# LCmeter0-LCD-8pinlcd-PIC-COMP.net
KiCad netlist of a schematic drawn in EAGLE
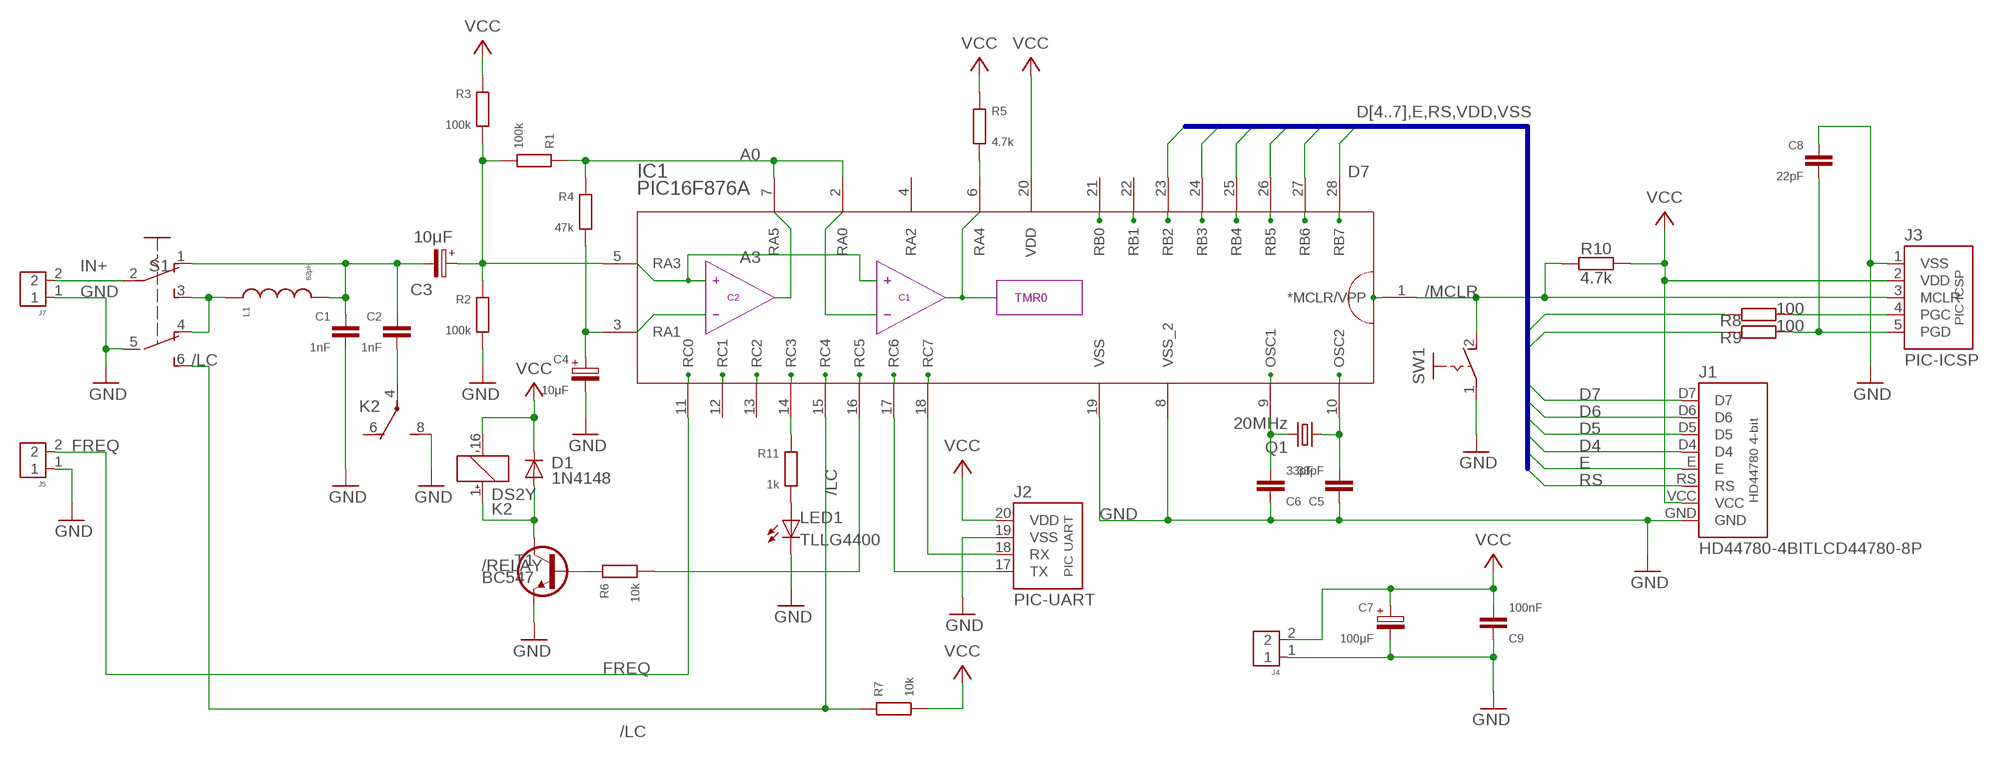
[diagram p0: schematic, sheet 1]

(export (version "E")
  (design (tool "Eeschema 10.0.6"))
  (components
    (comp (ref "C1")
      (value "1nF")
      (footprint "eagle-import:C050-025X060")
      (libsource (lib "eagle-import") (part "C025-025X060"))
    )
    (comp (ref "C2")
      (value "1nF")
      (footprint "eagle-import:C050-025X060")
      (libsource (lib "eagle-import") (part "C025-025X060"))
    )
    (comp (ref "C3")
      (value "10μF")
      (footprint "eagle-import:E2,5-4")
      (libsource (lib "eagle-import") (part "CPOLE2,5-4"))
    )
    (comp (ref "C4")
      (value "10μF")
      (footprint "eagle-import:E2,5-4")
      (libsource (lib "eagle-import") (part "CPOLE2,5-4"))
    )
    (comp (ref "C5")
      (value "33pF")
      (footprint "eagle-import:C025-020X036")
      (libsource (lib "eagle-import") (part "C025-020X036"))
    )
    (comp (ref "C6")
      (value "33pF")
      (footprint "eagle-import:C025-020X036")
      (libsource (lib "eagle-import") (part "C025-020X036"))
    )
    (comp (ref "C7")
      (value "100μF")
      (footprint "eagle-import:E2,5-5")
      (libsource (lib "eagle-import") (part "CPOLE2.5-5"))
    )
    (comp (ref "C8")
      (value "22pF")
      (footprint "eagle-import:C050-020X036")
      (libsource (lib "eagle-import") (part "C050-020X036"))
    )
    (comp (ref "C9")
      (value "100nF")
      (footprint "eagle-import:C025-020X036_V")
      (libsource (lib "eagle-import") (part "C025-020X036/V"))
    )
    (comp (ref "D1")
      (value "1N4148")
      (footprint "eagle-import:DO34-7")
      (libsource (lib "eagle-import") (part "1N414834-7"))
    )
    (comp (ref "IC1")
      (value "PIC16F876A")
      (footprint "eagle-import:DIL28-3")
      (libsource (lib "eagle-import") (part "PIC16F876A-X/SP-COMP-B-A"))
    )
    (comp (ref "J1")
      (value "HD44780-4BITLCD44780-8P")
      (footprint "eagle-import:CONN-LCD44780")
      (libsource (lib "eagle-import") (part "HD44780-4BITLCD44780-8P"))
    )
    (comp (ref "J2")
      (value "PIC-UART")
      (footprint "eagle-import:PIC-UART")
      (libsource (lib "eagle-import") (part "PIC-UART"))
    )
    (comp (ref "J3")
      (value "PIC-ICSP")
      (footprint "eagle-import:PIC-ICSP")
      (libsource (lib "eagle-import") (part "PIC-ICSPICSP"))
    )
    (comp (ref "J4")
      (value "J4")
      (footprint "eagle-import:CONN-2P")
      (libsource (lib "eagle-import") (part "CONN-2P2P/H"))
    )
    (comp (ref "J5")
      (value "CONN-2P2P/V")
      (footprint "eagle-import:CONN-2P-V")
      (libsource (lib "eagle-import") (part "CONN-2P2P/V"))
    )
    (comp (ref "J7")
      (value "CONN-2P2P/V")
      (footprint "eagle-import:CONN-2P-V")
      (libsource (lib "eagle-import") (part "CONN-2P2P/V"))
    )
    (comp (ref "K2")
      (value "DS2Y")
      (footprint "eagle-import:DS2Y")
      (fields (field (name "MPN") "DS2Y-S-DC5V"))
      (libsource (lib "eagle-import") (part "DS2Y-S-DC5V"))
    )
    (comp (ref "L1")
      (value "82μH")
      (footprint "eagle-import:0207_10")
      (libsource (lib "eagle-import") (part "LAXIAL"))
    )
    (comp (ref "LED1")
      (value "TLLG4400")
      (footprint "eagle-import:LED3MM")
      (fields (field (name "MF") "VISHAY SEMICONDUCTOR"))
      (libsource (lib "eagle-import") (part "TLLG4400"))
    )
    (comp (ref "Q1")
      (value "20MHz")
      (footprint "eagle-import:HC49")
      (libsource (lib "eagle-import") (part "CRYSTALHC49"))
    )
    (comp (ref "R1")
      (value "100k")
      (footprint "eagle-import:0202_7")
      (libsource (lib "eagle-import") (part "R0202/7"))
    )
    (comp (ref "R2")
      (value "100k")
      (footprint "eagle-import:0202_7")
      (libsource (lib "eagle-import") (part "R0202/7"))
    )
    (comp (ref "R3")
      (value "100k")
      (footprint "eagle-import:0202_7")
      (libsource (lib "eagle-import") (part "R0202/7"))
    )
    (comp (ref "R4")
      (value "47k")
      (footprint "eagle-import:0202_7")
      (libsource (lib "eagle-import") (part "R0202/7"))
    )
    (comp (ref "R5")
      (value "4.7k")
      (footprint "eagle-import:0202_7")
      (libsource (lib "eagle-import") (part "R0202/7"))
    )
    (comp (ref "R6")
      (value "10k")
      (footprint "eagle-import:0202_7-V")
      (libsource (lib "eagle-import") (part "R0202/7-V"))
    )
    (comp (ref "R7")
      (value "10k")
      (footprint "eagle-import:0202_10-V")
      (libsource (lib "eagle-import") (part "R0202/10-V"))
    )
    (comp (ref "R8")
      (value "100")
      (footprint "eagle-import:0202_7-V")
      (libsource (lib "eagle-import") (part "R0202/7-V"))
    )
    (comp (ref "R9")
      (value "100")
      (footprint "eagle-import:0202_5-V")
      (libsource (lib "eagle-import") (part "R0202/5-V"))
    )
    (comp (ref "R10")
      (value "4.7k")
      (footprint "eagle-import:0202_7")
      (libsource (lib "eagle-import") (part "R0202/7"))
    )
    (comp (ref "R11")
      (value "1k")
      (footprint "eagle-import:0202_5-V")
      (libsource (lib "eagle-import") (part "R0202/5-V"))
    )
    (comp (ref "S1")
      (value "SL-SW-2P-2T")
      (footprint "eagle-import:SLSW-2P2T")
      (libsource (lib "eagle-import") (part "SL-SW-2P-2T"))
    )
    (comp (ref "SW1")
      (value "PB-1P-1T")
      (footprint "eagle-import:PB-1P1T")
      (libsource (lib "eagle-import") (part "PB-1P-1T"))
    )
    (comp (ref "T1")
      (value "BC547")
      (footprint "eagle-import:TO92-CBE-A")
      (libsource (lib "eagle-import") (part "BC547CBE-A"))
    )
  )
  (nets
    (net (code "3") (name "/A0") (class "Default")
      (node (ref "IC1") (pin "2") (pinfunction "RA0_2") (pintype "passive"))
      (node (ref "IC1") (pin "7") (pinfunction "RA5_7") (pintype "passive"))
      (node (ref "R1") (pin "2") (pinfunction "2_2") (pintype "passive"))
      (node (ref "R4") (pin "2") (pinfunction "2_2") (pintype "passive"))
    )
    (net (code "4") (name "/A3") (class "Default")
      (node (ref "C3") (pin "+") (pinfunction "+_+") (pintype "passive"))
      (node (ref "IC1") (pin "5") (pinfunction "RA3_5") (pintype "passive"))
      (node (ref "R1") (pin "1") (pinfunction "1_1") (pintype "passive"))
      (node (ref "R2") (pin "2") (pinfunction "2_2") (pintype "passive"))
      (node (ref "R3") (pin "1") (pinfunction "1_1") (pintype "passive"))
    )
    (net (code "5") (name "/D4") (class "Default")
      (node (ref "IC1") (pin "25") (pinfunction "RB4_25") (pintype "passive"))
      (node (ref "J1") (pin "D4") (pinfunction "D4_D4") (pintype "passive"))
    )
    (net (code "6") (name "/D5") (class "Default")
      (node (ref "IC1") (pin "26") (pinfunction "RB5_26") (pintype "passive"))
      (node (ref "J1") (pin "D5") (pinfunction "D5_D5") (pintype "passive"))
    )
    (net (code "7") (name "/D6") (class "Default")
      (node (ref "IC1") (pin "27") (pinfunction "RB6_27") (pintype "passive"))
      (node (ref "J1") (pin "D6") (pinfunction "D6_D6") (pintype "passive"))
      (node (ref "R8") (pin "2") (pinfunction "2_2") (pintype "passive"))
    )
    (net (code "8") (name "/D7") (class "Default")
      (node (ref "IC1") (pin "28") (pinfunction "RB7_28") (pintype "passive"))
      (node (ref "J1") (pin "D7") (pinfunction "D7_D7") (pintype "passive"))
      (node (ref "R9") (pin "2") (pinfunction "2_2") (pintype "passive"))
    )
    (net (code "9") (name "/E") (class "Default")
      (node (ref "IC1") (pin "24") (pinfunction "RB3_24") (pintype "passive"))
      (node (ref "J1") (pin "E") (pinfunction "E_E") (pintype "passive"))
    )
    (net (code "10") (name "/FREQ") (class "Default")
      (node (ref "IC1") (pin "11") (pinfunction "RC0_11") (pintype "passive"))
      (node (ref "J5") (pin "2") (pinfunction "2_2") (pintype "bidirectional"))
    )
    (net (code "11") (name "/IN+") (class "Default")
      (node (ref "J7") (pin "2") (pinfunction "2_2") (pintype "bidirectional"))
      (node (ref "S1") (pin "2") (pinfunction "P_2") (pintype "passive"))
    )
    (net (code "12") (name "/RS") (class "Default")
      (node (ref "IC1") (pin "23") (pinfunction "RB2_23") (pintype "passive"))
      (node (ref "J1") (pin "RS") (pinfunction "RS_RS") (pintype "passive"))
    )
    (net (code "14") (name "/{slash}LC") (class "Default")
      (node (ref "IC1") (pin "15") (pinfunction "RC4_15") (pintype "passive"))
      (node (ref "R7") (pin "2") (pinfunction "2_2") (pintype "passive"))
      (node (ref "S1") (pin "6") (pinfunction "S1_6") (pintype "passive"))
    )
    (net (code "15") (name "/{slash}MCLR") (class "Default")
      (node (ref "IC1") (pin "1") (pinfunction "*MCLR/VPP_1") (pintype "passive"))
      (node (ref "J3") (pin "3") (pinfunction "MCLR_3") (pintype "passive"))
      (node (ref "R10") (pin "2") (pinfunction "2_2") (pintype "passive"))
      (node (ref "SW1") (pin "2") (pinfunction "S_2") (pintype "passive"))
    )
    (net (code "16") (name "/{slash}RELAY") (class "Default")
      (node (ref "D1") (pin "A") (pinfunction "A_A") (pintype "passive"))
      (node (ref "K2") (pin "1") (pinfunction "+_1") (pintype "passive"))
      (node (ref "T1") (pin "C") (pinfunction "C_C") (pintype "passive"))
    )
    (net (code "17") (name "GND") (class "Default")
      (node (ref "C1") (pin "2") (pinfunction "2_2") (pintype "passive"))
      (node (ref "C4") (pin "-") (pinfunction "-_-") (pintype "passive"))
      (node (ref "C5") (pin "1") (pinfunction "1_1") (pintype "passive"))
      (node (ref "C6") (pin "1") (pinfunction "1_1") (pintype "passive"))
      (node (ref "C7") (pin "-") (pinfunction "-_-") (pintype "passive"))
      (node (ref "C8") (pin "1") (pinfunction "1_1") (pintype "passive"))
      (node (ref "C9") (pin "1") (pinfunction "1_1") (pintype "passive"))
      (node (ref "IC1") (pin "19") (pinfunction "VSS_19") (pintype "passive"))
      (node (ref "IC1") (pin "8") (pinfunction "VSS_2_8") (pintype "passive"))
      (node (ref "J1") (pin "GND") (pinfunction "GND_GND") (pintype "passive"))
      (node (ref "J2") (pin "19") (pinfunction "VSS_19") (pintype "passive"))
      (node (ref "J3") (pin "1") (pinfunction "VSS_1") (pintype "passive"))
      (node (ref "J4") (pin "1") (pinfunction "1_1") (pintype "bidirectional"))
      (node (ref "J5") (pin "1") (pinfunction "1_1") (pintype "bidirectional"))
      (node (ref "J7") (pin "1") (pinfunction "1_1") (pintype "bidirectional"))
      (node (ref "K2") (pin "8") (pinfunction "S_8") (pintype "passive"))
      (node (ref "LED1") (pin "K") (pinfunction "C_K") (pintype "passive"))
      (node (ref "R2") (pin "1") (pinfunction "1_1") (pintype "passive"))
      (node (ref "S1") (pin "5") (pinfunction "P1_5") (pintype "passive"))
      (node (ref "SW1") (pin "1") (pinfunction "P_1") (pintype "passive"))
      (node (ref "T1") (pin "E") (pinfunction "E_E") (pintype "passive"))
    )
    (net (code "18") (name "Net-(IC1-OSC1)") (class "Default")
      (node (ref "C6") (pin "2") (pinfunction "2_2") (pintype "passive"))
      (node (ref "IC1") (pin "9") (pinfunction "OSC1_9") (pintype "passive"))
      (node (ref "Q1") (pin "2") (pinfunction "2_2") (pintype "passive"))
    )
    (net (code "19") (name "Net-(IC1-OSC2)") (class "Default")
      (node (ref "C5") (pin "2") (pinfunction "2_2") (pintype "passive"))
      (node (ref "IC1") (pin "10") (pinfunction "OSC2_10") (pintype "passive"))
      (node (ref "Q1") (pin "1") (pinfunction "1_1") (pintype "passive"))
    )
    (net (code "20") (name "Net-(IC1-RA1)") (class "Default")
      (node (ref "C4") (pin "+") (pinfunction "+_+") (pintype "passive"))
      (node (ref "IC1") (pin "3") (pinfunction "RA1_3") (pintype "passive"))
      (node (ref "R4") (pin "1") (pinfunction "1_1") (pintype "passive"))
    )
    (net (code "21") (name "Net-(IC1-RA4)") (class "Default")
      (node (ref "IC1") (pin "6") (pinfunction "RA4_6") (pintype "passive"))
      (node (ref "R5") (pin "1") (pinfunction "1_1") (pintype "passive"))
    )
    (net (code "22") (name "Net-(IC1-RC3)") (class "Default")
      (node (ref "IC1") (pin "14") (pinfunction "RC3_14") (pintype "passive"))
      (node (ref "R11") (pin "2") (pinfunction "2_2") (pintype "passive"))
    )
    (net (code "23") (name "Net-(IC1-RC5)") (class "Default")
      (node (ref "IC1") (pin "16") (pinfunction "RC5_16") (pintype "passive"))
      (node (ref "R6") (pin "1") (pinfunction "1_1") (pintype "passive"))
    )
    (net (code "24") (name "Net-(IC1-RC6)") (class "Default")
      (node (ref "IC1") (pin "17") (pinfunction "RC6_17") (pintype "passive"))
      (node (ref "J2") (pin "17") (pinfunction "TX_17") (pintype "passive"))
    )
    (net (code "25") (name "Net-(IC1-RC7)") (class "Default")
      (node (ref "IC1") (pin "18") (pinfunction "RC7_18") (pintype "passive"))
      (node (ref "J2") (pin "18") (pinfunction "RX_18") (pintype "passive"))
    )
    (net (code "26") (name "Net-(J3-PGC)") (class "Default")
      (node (ref "J3") (pin "4") (pinfunction "PGC_4") (pintype "passive"))
      (node (ref "R8") (pin "1") (pinfunction "1_1") (pintype "passive"))
    )
    (net (code "27") (name "Net-(J3-PGD)") (class "Default")
      (node (ref "C8") (pin "2") (pinfunction "2_2") (pintype "passive"))
      (node (ref "J3") (pin "5") (pinfunction "PGD_5") (pintype "passive"))
      (node (ref "R9") (pin "1") (pinfunction "1_1") (pintype "passive"))
    )
    (net (code "28") (name "Net-(K2B-P)") (class "Default")
      (node (ref "C2") (pin "2") (pinfunction "2_2") (pintype "passive"))
      (node (ref "K2") (pin "4") (pinfunction "P_4") (pintype "passive"))
    )
    (net (code "29") (name "Net-(LED1-PadA)") (class "Default")
      (node (ref "LED1") (pin "A") (pinfunction "A_A") (pintype "passive"))
      (node (ref "R11") (pin "1") (pinfunction "1_1") (pintype "passive"))
    )
    (net (code "30") (name "Net-(R6-Pad2)") (class "Default")
      (node (ref "R6") (pin "2") (pinfunction "2_2") (pintype "passive"))
      (node (ref "T1") (pin "B") (pinfunction "B_B") (pintype "passive"))
    )
    (net (code "31") (name "Net-(S1-O)") (class "Default")
      (node (ref "C1") (pin "1") (pinfunction "1_1") (pintype "passive"))
      (node (ref "C2") (pin "1") (pinfunction "1_1") (pintype "passive"))
      (node (ref "C3") (pin "-") (pinfunction "-_-") (pintype "passive"))
      (node (ref "L1") (pin "2") (pinfunction "2_2") (pintype "passive"))
      (node (ref "S1") (pin "1") (pinfunction "O_1") (pintype "passive"))
    )
    (net (code "32") (name "Net-(S1-O1)") (class "Default")
      (node (ref "L1") (pin "1") (pinfunction "1_1") (pintype "passive"))
      (node (ref "S1") (pin "3") (pinfunction "S_3") (pintype "passive"))
      (node (ref "S1") (pin "4") (pinfunction "O1_4") (pintype "passive"))
    )
    (net (code "33") (name "VCC") (class "Default")
      (node (ref "C7") (pin "+") (pinfunction "+_+") (pintype "passive"))
      (node (ref "C9") (pin "2") (pinfunction "2_2") (pintype "passive"))
      (node (ref "D1") (pin "C") (pinfunction "C_C") (pintype "passive"))
      (node (ref "IC1") (pin "20") (pinfunction "VDD_20") (pintype "passive"))
      (node (ref "J1") (pin "VCC") (pinfunction "VCC_VCC") (pintype "passive"))
      (node (ref "J2") (pin "20") (pinfunction "VDD_20") (pintype "passive"))
      (node (ref "J3") (pin "2") (pinfunction "VDD_2") (pintype "passive"))
      (node (ref "J4") (pin "2") (pinfunction "2_2") (pintype "bidirectional"))
      (node (ref "K2") (pin "16") (pinfunction "-_16") (pintype "passive"))
      (node (ref "R10") (pin "1") (pinfunction "1_1") (pintype "passive"))
      (node (ref "R3") (pin "2") (pinfunction "2_2") (pintype "passive"))
      (node (ref "R5") (pin "2") (pinfunction "2_2") (pintype "passive"))
      (node (ref "R7") (pin "1") (pinfunction "1_1") (pintype "passive"))
    )
    (net (code "34") (name "unconnected-(IC1-RA2-Pad4)") (class "Default")
      (node (ref "IC1") (pin "4") (pinfunction "RA2_4") (pintype "passive"))
    )
    (net (code "35") (name "unconnected-(IC1-RB0-Pad21)") (class "Default")
      (node (ref "IC1") (pin "21") (pinfunction "RB0_21") (pintype "passive"))
    )
    (net (code "36") (name "unconnected-(IC1-RB1-Pad22)") (class "Default")
      (node (ref "IC1") (pin "22") (pinfunction "RB1_22") (pintype "passive"))
    )
    (net (code "37") (name "unconnected-(IC1-RC1-Pad12)") (class "Default")
      (node (ref "IC1") (pin "12") (pinfunction "RC1_12") (pintype "passive"))
    )
    (net (code "38") (name "unconnected-(IC1-RC2-Pad13)") (class "Default")
      (node (ref "IC1") (pin "13") (pinfunction "RC2_13") (pintype "passive"))
    )
    (net (code "39") (name "unconnected-(K2B-O-Pad6)") (class "Default")
      (node (ref "K2") (pin "6") (pinfunction "O_6") (pintype "passive"))
    )
  )
)
